# CHRMN-PROT-SHIELD.net
KiCad netlist of a schematic drawn in EAGLE
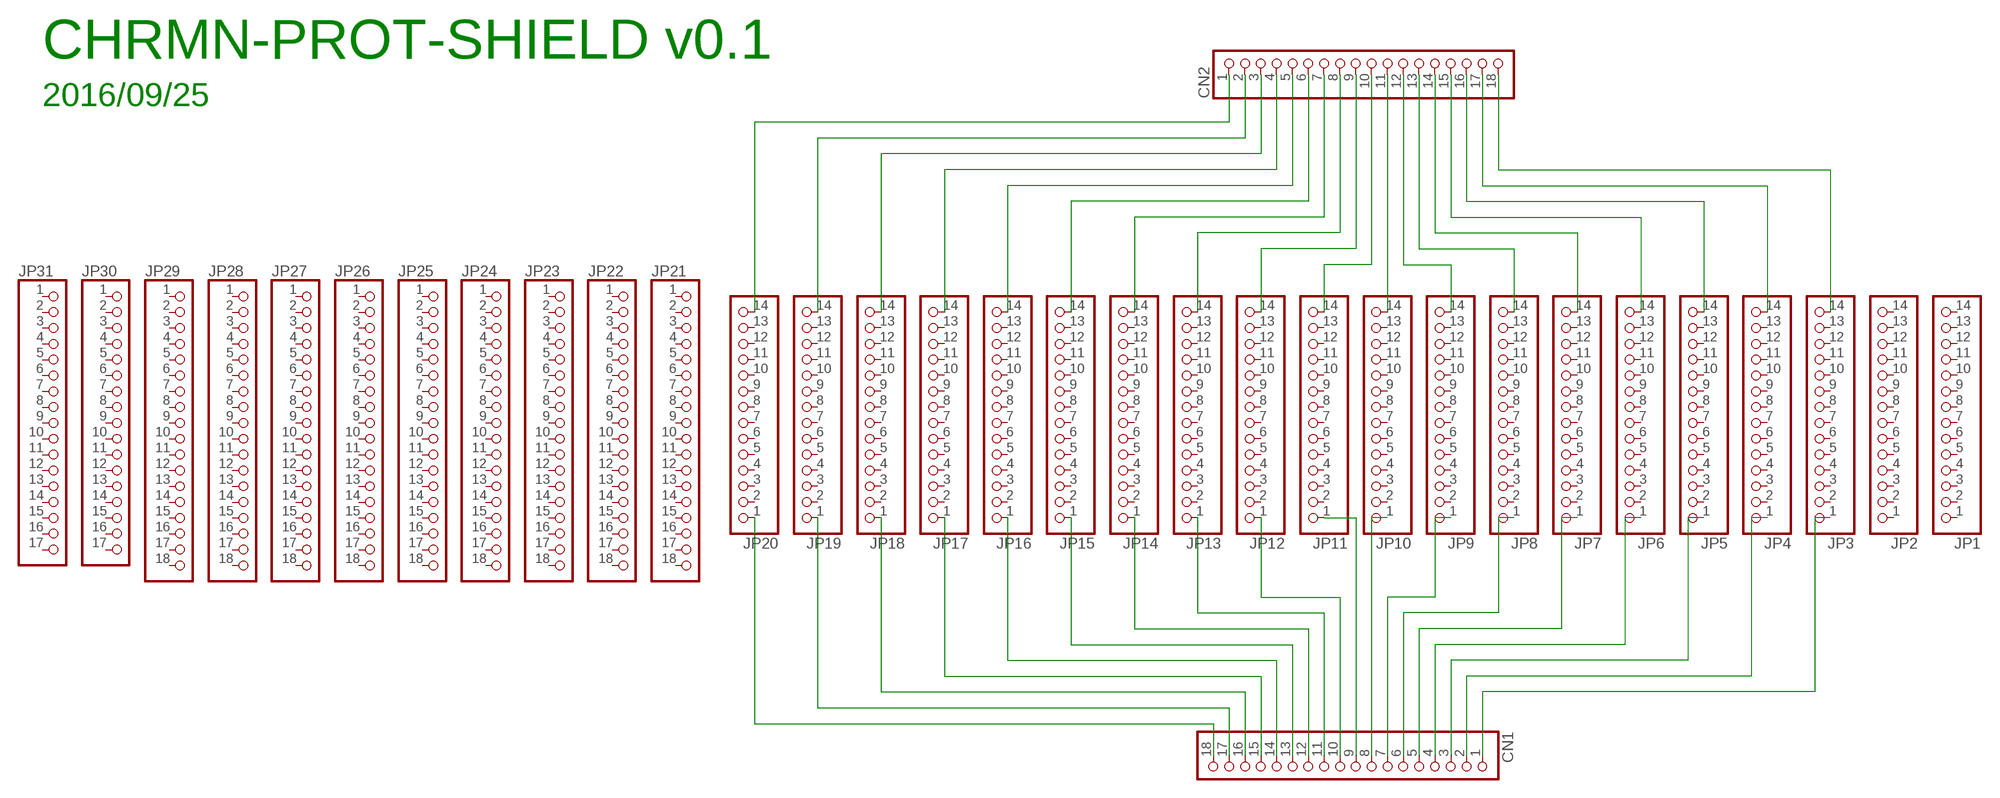
[diagram p0: schematic, sheet 1]

(export (version "E")
  (design (tool "Eeschema 10.0.6"))
  (components
    (comp (ref "CN1")
      (value "PINHD-1X18")
      (footprint "eagle-import:1X18")
      (libsource (lib "eagle-import") (part "pinhead_PINHD-1X18"))
    )
    (comp (ref "CN2")
      (value "PINHD-1X18")
      (footprint "eagle-import:1X18")
      (libsource (lib "eagle-import") (part "pinhead_PINHD-1X18"))
    )
    (comp (ref "JP1")
      (value "PINHD-1X141X14-N")
      (footprint "eagle-import:N-PHEAD-1_14")
      (libsource (lib "eagle-import") (part "PINHD-1X141X14-N"))
    )
    (comp (ref "JP2")
      (value "PINHD-1X141X14-N")
      (footprint "eagle-import:N-PHEAD-1_14")
      (libsource (lib "eagle-import") (part "PINHD-1X141X14-N"))
    )
    (comp (ref "JP3")
      (value "PINHD-1X141X14-N")
      (footprint "eagle-import:N-PHEAD-1_14")
      (libsource (lib "eagle-import") (part "PINHD-1X141X14-N"))
    )
    (comp (ref "JP4")
      (value "PINHD-1X141X14-N")
      (footprint "eagle-import:N-PHEAD-1_14")
      (libsource (lib "eagle-import") (part "PINHD-1X141X14-N"))
    )
    (comp (ref "JP5")
      (value "PINHD-1X141X14-N")
      (footprint "eagle-import:N-PHEAD-1_14")
      (libsource (lib "eagle-import") (part "PINHD-1X141X14-N"))
    )
    (comp (ref "JP6")
      (value "PINHD-1X141X14-N")
      (footprint "eagle-import:N-PHEAD-1_14")
      (libsource (lib "eagle-import") (part "PINHD-1X141X14-N"))
    )
    (comp (ref "JP7")
      (value "PINHD-1X141X14-N")
      (footprint "eagle-import:N-PHEAD-1_14")
      (libsource (lib "eagle-import") (part "PINHD-1X141X14-N"))
    )
    (comp (ref "JP8")
      (value "PINHD-1X141X14-N")
      (footprint "eagle-import:N-PHEAD-1_14")
      (libsource (lib "eagle-import") (part "PINHD-1X141X14-N"))
    )
    (comp (ref "JP9")
      (value "PINHD-1X141X14-N")
      (footprint "eagle-import:N-PHEAD-1_14")
      (libsource (lib "eagle-import") (part "PINHD-1X141X14-N"))
    )
    (comp (ref "JP10")
      (value "PINHD-1X141X14-N")
      (footprint "eagle-import:N-PHEAD-1_14")
      (libsource (lib "eagle-import") (part "PINHD-1X141X14-N"))
    )
    (comp (ref "JP11")
      (value "PINHD-1X141X14-N")
      (footprint "eagle-import:N-PHEAD-1_14")
      (libsource (lib "eagle-import") (part "PINHD-1X141X14-N"))
    )
    (comp (ref "JP12")
      (value "PINHD-1X141X14-N")
      (footprint "eagle-import:N-PHEAD-1_14")
      (libsource (lib "eagle-import") (part "PINHD-1X141X14-N"))
    )
    (comp (ref "JP13")
      (value "PINHD-1X141X14-N")
      (footprint "eagle-import:N-PHEAD-1_14")
      (libsource (lib "eagle-import") (part "PINHD-1X141X14-N"))
    )
    (comp (ref "JP14")
      (value "PINHD-1X141X14-N")
      (footprint "eagle-import:N-PHEAD-1_14")
      (libsource (lib "eagle-import") (part "PINHD-1X141X14-N"))
    )
    (comp (ref "JP15")
      (value "PINHD-1X141X14-N")
      (footprint "eagle-import:N-PHEAD-1_14")
      (libsource (lib "eagle-import") (part "PINHD-1X141X14-N"))
    )
    (comp (ref "JP16")
      (value "PINHD-1X141X14-N")
      (footprint "eagle-import:N-PHEAD-1_14")
      (libsource (lib "eagle-import") (part "PINHD-1X141X14-N"))
    )
    (comp (ref "JP17")
      (value "PINHD-1X141X14-N")
      (footprint "eagle-import:N-PHEAD-1_14")
      (libsource (lib "eagle-import") (part "PINHD-1X141X14-N"))
    )
    (comp (ref "JP18")
      (value "PINHD-1X141X14-N")
      (footprint "eagle-import:N-PHEAD-1_14")
      (libsource (lib "eagle-import") (part "PINHD-1X141X14-N"))
    )
    (comp (ref "JP19")
      (value "PINHD-1X141X14-N")
      (footprint "eagle-import:N-PHEAD-1_14")
      (libsource (lib "eagle-import") (part "PINHD-1X141X14-N"))
    )
    (comp (ref "JP20")
      (value "PINHD-1X141X14-N")
      (footprint "eagle-import:N-PHEAD-1_14")
      (libsource (lib "eagle-import") (part "PINHD-1X141X14-N"))
    )
    (comp (ref "JP21")
      (value "PINHD-1X181X18-N")
      (footprint "eagle-import:N-PHEAD-1_18")
      (libsource (lib "eagle-import") (part "PINHD-1X181X18-N"))
    )
    (comp (ref "JP22")
      (value "PINHD-1X181X18-N")
      (footprint "eagle-import:N-PHEAD-1_18")
      (libsource (lib "eagle-import") (part "PINHD-1X181X18-N"))
    )
    (comp (ref "JP23")
      (value "PINHD-1X181X18-N")
      (footprint "eagle-import:N-PHEAD-1_18")
      (libsource (lib "eagle-import") (part "PINHD-1X181X18-N"))
    )
    (comp (ref "JP24")
      (value "PINHD-1X181X18-N")
      (footprint "eagle-import:N-PHEAD-1_18")
      (libsource (lib "eagle-import") (part "PINHD-1X181X18-N"))
    )
    (comp (ref "JP25")
      (value "PINHD-1X181X18-N")
      (footprint "eagle-import:N-PHEAD-1_18")
      (libsource (lib "eagle-import") (part "PINHD-1X181X18-N"))
    )
    (comp (ref "JP26")
      (value "PINHD-1X181X18-N")
      (footprint "eagle-import:N-PHEAD-1_18")
      (libsource (lib "eagle-import") (part "PINHD-1X181X18-N"))
    )
    (comp (ref "JP27")
      (value "PINHD-1X181X18-N")
      (footprint "eagle-import:N-PHEAD-1_18")
      (libsource (lib "eagle-import") (part "PINHD-1X181X18-N"))
    )
    (comp (ref "JP28")
      (value "PINHD-1X181X18-N")
      (footprint "eagle-import:N-PHEAD-1_18")
      (libsource (lib "eagle-import") (part "PINHD-1X181X18-N"))
    )
    (comp (ref "JP29")
      (value "PINHD-1X181X18-N")
      (footprint "eagle-import:N-PHEAD-1_18")
      (libsource (lib "eagle-import") (part "PINHD-1X181X18-N"))
    )
    (comp (ref "JP30")
      (value "PINHD-1X171X17N")
      (footprint "eagle-import:N-PHEAD-1_17")
      (libsource (lib "eagle-import") (part "PINHD-1X171X17N"))
    )
    (comp (ref "JP31")
      (value "PINHD-1X171X17N")
      (footprint "eagle-import:N-PHEAD-1_17")
      (libsource (lib "eagle-import") (part "PINHD-1X171X17N"))
    )
  )
  (nets
    (net (code "1") (name "Net-(CN1-Pad1)") (class "Default")
      (node (ref "CN1") (pin "1") (pinfunction "1_1") (pintype "passive"))
      (node (ref "JP3") (pin "1") (pinfunction "1_1") (pintype "passive"))
    )
    (net (code "2") (name "Net-(CN1-Pad2)") (class "Default")
      (node (ref "CN1") (pin "2") (pinfunction "2_2") (pintype "passive"))
      (node (ref "JP4") (pin "1") (pinfunction "1_1") (pintype "passive"))
    )
    (net (code "3") (name "Net-(CN1-Pad3)") (class "Default")
      (node (ref "CN1") (pin "3") (pinfunction "3_3") (pintype "passive"))
      (node (ref "JP5") (pin "1") (pinfunction "1_1") (pintype "passive"))
    )
    (net (code "4") (name "Net-(CN1-Pad4)") (class "Default")
      (node (ref "CN1") (pin "4") (pinfunction "4_4") (pintype "passive"))
      (node (ref "JP6") (pin "1") (pinfunction "1_1") (pintype "passive"))
    )
    (net (code "5") (name "Net-(CN1-Pad5)") (class "Default")
      (node (ref "CN1") (pin "5") (pinfunction "5_5") (pintype "passive"))
      (node (ref "JP7") (pin "1") (pinfunction "1_1") (pintype "passive"))
    )
    (net (code "6") (name "Net-(CN1-Pad6)") (class "Default")
      (node (ref "CN1") (pin "6") (pinfunction "6_6") (pintype "passive"))
      (node (ref "JP8") (pin "1") (pinfunction "1_1") (pintype "passive"))
    )
    (net (code "7") (name "Net-(CN1-Pad7)") (class "Default")
      (node (ref "CN1") (pin "7") (pinfunction "7_7") (pintype "passive"))
      (node (ref "JP9") (pin "1") (pinfunction "1_1") (pintype "passive"))
    )
    (net (code "8") (name "Net-(CN1-Pad8)") (class "Default")
      (node (ref "CN1") (pin "8") (pinfunction "8_8") (pintype "passive"))
      (node (ref "JP10") (pin "1") (pinfunction "1_1") (pintype "passive"))
    )
    (net (code "9") (name "Net-(CN1-Pad9)") (class "Default")
      (node (ref "CN1") (pin "9") (pinfunction "9_9") (pintype "passive"))
      (node (ref "JP11") (pin "1") (pinfunction "1_1") (pintype "passive"))
    )
    (net (code "10") (name "Net-(CN1-Pad10)") (class "Default")
      (node (ref "CN1") (pin "10") (pinfunction "10_10") (pintype "passive"))
      (node (ref "JP12") (pin "1") (pinfunction "1_1") (pintype "passive"))
    )
    (net (code "11") (name "Net-(CN1-Pad11)") (class "Default")
      (node (ref "CN1") (pin "11") (pinfunction "11_11") (pintype "passive"))
      (node (ref "JP13") (pin "1") (pinfunction "1_1") (pintype "passive"))
    )
    (net (code "12") (name "Net-(CN1-Pad12)") (class "Default")
      (node (ref "CN1") (pin "12") (pinfunction "12_12") (pintype "passive"))
      (node (ref "JP14") (pin "1") (pinfunction "1_1") (pintype "passive"))
    )
    (net (code "13") (name "Net-(CN1-Pad13)") (class "Default")
      (node (ref "CN1") (pin "13") (pinfunction "13_13") (pintype "passive"))
      (node (ref "JP15") (pin "1") (pinfunction "1_1") (pintype "passive"))
    )
    (net (code "14") (name "Net-(CN1-Pad14)") (class "Default")
      (node (ref "CN1") (pin "14") (pinfunction "14_14") (pintype "passive"))
      (node (ref "JP16") (pin "1") (pinfunction "1_1") (pintype "passive"))
    )
    (net (code "15") (name "Net-(CN1-Pad15)") (class "Default")
      (node (ref "CN1") (pin "15") (pinfunction "15_15") (pintype "passive"))
      (node (ref "JP17") (pin "1") (pinfunction "1_1") (pintype "passive"))
    )
    (net (code "16") (name "Net-(CN1-Pad16)") (class "Default")
      (node (ref "CN1") (pin "16") (pinfunction "16_16") (pintype "passive"))
      (node (ref "JP18") (pin "1") (pinfunction "1_1") (pintype "passive"))
    )
    (net (code "17") (name "Net-(CN1-Pad17)") (class "Default")
      (node (ref "CN1") (pin "17") (pinfunction "17_17") (pintype "passive"))
      (node (ref "JP19") (pin "1") (pinfunction "1_1") (pintype "passive"))
    )
    (net (code "18") (name "Net-(CN1-Pad18)") (class "Default")
      (node (ref "CN1") (pin "18") (pinfunction "18_18") (pintype "passive"))
      (node (ref "JP20") (pin "1") (pinfunction "1_1") (pintype "passive"))
    )
    (net (code "19") (name "Net-(CN2-Pad1)") (class "Default")
      (node (ref "CN2") (pin "1") (pinfunction "1_1") (pintype "passive"))
      (node (ref "JP20") (pin "14") (pinfunction "14_14") (pintype "passive"))
    )
    (net (code "20") (name "Net-(CN2-Pad2)") (class "Default")
      (node (ref "CN2") (pin "2") (pinfunction "2_2") (pintype "passive"))
      (node (ref "JP19") (pin "14") (pinfunction "14_14") (pintype "passive"))
    )
    (net (code "21") (name "Net-(CN2-Pad3)") (class "Default")
      (node (ref "CN2") (pin "3") (pinfunction "3_3") (pintype "passive"))
      (node (ref "JP18") (pin "14") (pinfunction "14_14") (pintype "passive"))
    )
    (net (code "22") (name "Net-(CN2-Pad4)") (class "Default")
      (node (ref "CN2") (pin "4") (pinfunction "4_4") (pintype "passive"))
      (node (ref "JP17") (pin "14") (pinfunction "14_14") (pintype "passive"))
    )
    (net (code "23") (name "Net-(CN2-Pad5)") (class "Default")
      (node (ref "CN2") (pin "5") (pinfunction "5_5") (pintype "passive"))
      (node (ref "JP16") (pin "14") (pinfunction "14_14") (pintype "passive"))
    )
    (net (code "24") (name "Net-(CN2-Pad6)") (class "Default")
      (node (ref "CN2") (pin "6") (pinfunction "6_6") (pintype "passive"))
      (node (ref "JP15") (pin "14") (pinfunction "14_14") (pintype "passive"))
    )
    (net (code "25") (name "Net-(CN2-Pad7)") (class "Default")
      (node (ref "CN2") (pin "7") (pinfunction "7_7") (pintype "passive"))
      (node (ref "JP14") (pin "14") (pinfunction "14_14") (pintype "passive"))
    )
    (net (code "26") (name "Net-(CN2-Pad8)") (class "Default")
      (node (ref "CN2") (pin "8") (pinfunction "8_8") (pintype "passive"))
      (node (ref "JP13") (pin "14") (pinfunction "14_14") (pintype "passive"))
    )
    (net (code "27") (name "Net-(CN2-Pad9)") (class "Default")
      (node (ref "CN2") (pin "9") (pinfunction "9_9") (pintype "passive"))
      (node (ref "JP12") (pin "14") (pinfunction "14_14") (pintype "passive"))
    )
    (net (code "28") (name "Net-(CN2-Pad10)") (class "Default")
      (node (ref "CN2") (pin "10") (pinfunction "10_10") (pintype "passive"))
      (node (ref "JP11") (pin "14") (pinfunction "14_14") (pintype "passive"))
    )
    (net (code "29") (name "Net-(CN2-Pad11)") (class "Default")
      (node (ref "CN2") (pin "11") (pinfunction "11_11") (pintype "passive"))
      (node (ref "JP10") (pin "14") (pinfunction "14_14") (pintype "passive"))
    )
    (net (code "30") (name "Net-(CN2-Pad12)") (class "Default")
      (node (ref "CN2") (pin "12") (pinfunction "12_12") (pintype "passive"))
      (node (ref "JP9") (pin "14") (pinfunction "14_14") (pintype "passive"))
    )
    (net (code "31") (name "Net-(CN2-Pad13)") (class "Default")
      (node (ref "CN2") (pin "13") (pinfunction "13_13") (pintype "passive"))
      (node (ref "JP8") (pin "14") (pinfunction "14_14") (pintype "passive"))
    )
    (net (code "32") (name "Net-(CN2-Pad14)") (class "Default")
      (node (ref "CN2") (pin "14") (pinfunction "14_14") (pintype "passive"))
      (node (ref "JP7") (pin "14") (pinfunction "14_14") (pintype "passive"))
    )
    (net (code "33") (name "Net-(CN2-Pad15)") (class "Default")
      (node (ref "CN2") (pin "15") (pinfunction "15_15") (pintype "passive"))
      (node (ref "JP6") (pin "14") (pinfunction "14_14") (pintype "passive"))
    )
    (net (code "34") (name "Net-(CN2-Pad16)") (class "Default")
      (node (ref "CN2") (pin "16") (pinfunction "16_16") (pintype "passive"))
      (node (ref "JP5") (pin "14") (pinfunction "14_14") (pintype "passive"))
    )
    (net (code "35") (name "Net-(CN2-Pad17)") (class "Default")
      (node (ref "CN2") (pin "17") (pinfunction "17_17") (pintype "passive"))
      (node (ref "JP4") (pin "14") (pinfunction "14_14") (pintype "passive"))
    )
    (net (code "36") (name "Net-(CN2-Pad18)") (class "Default")
      (node (ref "CN2") (pin "18") (pinfunction "18_18") (pintype "passive"))
      (node (ref "JP3") (pin "14") (pinfunction "14_14") (pintype "passive"))
    )
    (net (code "37") (name "unconnected-(JP1-Pad1)") (class "Default")
      (node (ref "JP1") (pin "1") (pinfunction "1_1") (pintype "passive"))
    )
    (net (code "38") (name "unconnected-(JP1-Pad2)") (class "Default")
      (node (ref "JP1") (pin "2") (pinfunction "2_2") (pintype "passive"))
    )
    (net (code "39") (name "unconnected-(JP1-Pad3)") (class "Default")
      (node (ref "JP1") (pin "3") (pinfunction "3_3") (pintype "passive"))
    )
    (net (code "40") (name "unconnected-(JP1-Pad4)") (class "Default")
      (node (ref "JP1") (pin "4") (pinfunction "4_4") (pintype "passive"))
    )
    (net (code "41") (name "unconnected-(JP1-Pad5)") (class "Default")
      (node (ref "JP1") (pin "5") (pinfunction "5_5") (pintype "passive"))
    )
    (net (code "42") (name "unconnected-(JP1-Pad6)") (class "Default")
      (node (ref "JP1") (pin "6") (pinfunction "6_6") (pintype "passive"))
    )
    (net (code "43") (name "unconnected-(JP1-Pad7)") (class "Default")
      (node (ref "JP1") (pin "7") (pinfunction "7_7") (pintype "passive"))
    )
    (net (code "44") (name "unconnected-(JP1-Pad8)") (class "Default")
      (node (ref "JP1") (pin "8") (pinfunction "8_8") (pintype "passive"))
    )
    (net (code "45") (name "unconnected-(JP1-Pad9)") (class "Default")
      (node (ref "JP1") (pin "9") (pinfunction "9_9") (pintype "passive"))
    )
    (net (code "46") (name "unconnected-(JP1-Pad10)") (class "Default")
      (node (ref "JP1") (pin "10") (pinfunction "10_10") (pintype "passive"))
    )
    (net (code "47") (name "unconnected-(JP1-Pad11)") (class "Default")
      (node (ref "JP1") (pin "11") (pinfunction "11_11") (pintype "passive"))
    )
    (net (code "48") (name "unconnected-(JP1-Pad12)") (class "Default")
      (node (ref "JP1") (pin "12") (pinfunction "12_12") (pintype "passive"))
    )
    (net (code "49") (name "unconnected-(JP1-Pad13)") (class "Default")
      (node (ref "JP1") (pin "13") (pinfunction "13_13") (pintype "passive"))
    )
    (net (code "50") (name "unconnected-(JP1-Pad14)") (class "Default")
      (node (ref "JP1") (pin "14") (pinfunction "14_14") (pintype "passive"))
    )
    (net (code "51") (name "unconnected-(JP2-Pad1)") (class "Default")
      (node (ref "JP2") (pin "1") (pinfunction "1_1") (pintype "passive"))
    )
    (net (code "52") (name "unconnected-(JP2-Pad2)") (class "Default")
      (node (ref "JP2") (pin "2") (pinfunction "2_2") (pintype "passive"))
    )
    (net (code "53") (name "unconnected-(JP2-Pad3)") (class "Default")
      (node (ref "JP2") (pin "3") (pinfunction "3_3") (pintype "passive"))
    )
    (net (code "54") (name "unconnected-(JP2-Pad4)") (class "Default")
      (node (ref "JP2") (pin "4") (pinfunction "4_4") (pintype "passive"))
    )
    (net (code "55") (name "unconnected-(JP2-Pad5)") (class "Default")
      (node (ref "JP2") (pin "5") (pinfunction "5_5") (pintype "passive"))
    )
    (net (code "56") (name "unconnected-(JP2-Pad6)") (class "Default")
      (node (ref "JP2") (pin "6") (pinfunction "6_6") (pintype "passive"))
    )
    (net (code "57") (name "unconnected-(JP2-Pad7)") (class "Default")
      (node (ref "JP2") (pin "7") (pinfunction "7_7") (pintype "passive"))
    )
    (net (code "58") (name "unconnected-(JP2-Pad8)") (class "Default")
      (node (ref "JP2") (pin "8") (pinfunction "8_8") (pintype "passive"))
    )
    (net (code "59") (name "unconnected-(JP2-Pad9)") (class "Default")
      (node (ref "JP2") (pin "9") (pinfunction "9_9") (pintype "passive"))
    )
    (net (code "60") (name "unconnected-(JP2-Pad10)") (class "Default")
      (node (ref "JP2") (pin "10") (pinfunction "10_10") (pintype "passive"))
    )
    (net (code "61") (name "unconnected-(JP2-Pad11)") (class "Default")
      (node (ref "JP2") (pin "11") (pinfunction "11_11") (pintype "passive"))
    )
    (net (code "62") (name "unconnected-(JP2-Pad12)") (class "Default")
      (node (ref "JP2") (pin "12") (pinfunction "12_12") (pintype "passive"))
    )
    (net (code "63") (name "unconnected-(JP2-Pad13)") (class "Default")
      (node (ref "JP2") (pin "13") (pinfunction "13_13") (pintype "passive"))
    )
    (net (code "64") (name "unconnected-(JP2-Pad14)") (class "Default")
      (node (ref "JP2") (pin "14") (pinfunction "14_14") (pintype "passive"))
    )
    (net (code "65") (name "unconnected-(JP3-Pad2)") (class "Default")
      (node (ref "JP3") (pin "2") (pinfunction "2_2") (pintype "passive"))
    )
    (net (code "66") (name "unconnected-(JP3-Pad3)") (class "Default")
      (node (ref "JP3") (pin "3") (pinfunction "3_3") (pintype "passive"))
    )
    (net (code "67") (name "unconnected-(JP3-Pad4)") (class "Default")
      (node (ref "JP3") (pin "4") (pinfunction "4_4") (pintype "passive"))
    )
    (net (code "68") (name "unconnected-(JP3-Pad5)") (class "Default")
      (node (ref "JP3") (pin "5") (pinfunction "5_5") (pintype "passive"))
    )
    (net (code "69") (name "unconnected-(JP3-Pad6)") (class "Default")
      (node (ref "JP3") (pin "6") (pinfunction "6_6") (pintype "passive"))
    )
    (net (code "70") (name "unconnected-(JP3-Pad7)") (class "Default")
      (node (ref "JP3") (pin "7") (pinfunction "7_7") (pintype "passive"))
    )
    (net (code "71") (name "unconnected-(JP3-Pad8)") (class "Default")
      (node (ref "JP3") (pin "8") (pinfunction "8_8") (pintype "passive"))
    )
    (net (code "72") (name "unconnected-(JP3-Pad9)") (class "Default")
      (node (ref "JP3") (pin "9") (pinfunction "9_9") (pintype "passive"))
    )
    (net (code "73") (name "unconnected-(JP3-Pad10)") (class "Default")
      (node (ref "JP3") (pin "10") (pinfunction "10_10") (pintype "passive"))
    )
    (net (code "74") (name "unconnected-(JP3-Pad11)") (class "Default")
      (node (ref "JP3") (pin "11") (pinfunction "11_11") (pintype "passive"))
    )
    (net (code "75") (name "unconnected-(JP3-Pad12)") (class "Default")
      (node (ref "JP3") (pin "12") (pinfunction "12_12") (pintype "passive"))
    )
    (net (code "76") (name "unconnected-(JP3-Pad13)") (class "Default")
      (node (ref "JP3") (pin "13") (pinfunction "13_13") (pintype "passive"))
    )
    (net (code "77") (name "unconnected-(JP4-Pad2)") (class "Default")
      (node (ref "JP4") (pin "2") (pinfunction "2_2") (pintype "passive"))
    )
    (net (code "78") (name "unconnected-(JP4-Pad3)") (class "Default")
      (node (ref "JP4") (pin "3") (pinfunction "3_3") (pintype "passive"))
    )
    (net (code "79") (name "unconnected-(JP4-Pad4)") (class "Default")
      (node (ref "JP4") (pin "4") (pinfunction "4_4") (pintype "passive"))
    )
    (net (code "80") (name "unconnected-(JP4-Pad5)") (class "Default")
      (node (ref "JP4") (pin "5") (pinfunction "5_5") (pintype "passive"))
    )
    (net (code "81") (name "unconnected-(JP4-Pad6)") (class "Default")
      (node (ref "JP4") (pin "6") (pinfunction "6_6") (pintype "passive"))
    )
    (net (code "82") (name "unconnected-(JP4-Pad7)") (class "Default")
      (node (ref "JP4") (pin "7") (pinfunction "7_7") (pintype "passive"))
    )
    (net (code "83") (name "unconnected-(JP4-Pad8)") (class "Default")
      (node (ref "JP4") (pin "8") (pinfunction "8_8") (pintype "passive"))
    )
    (net (code "84") (name "unconnected-(JP4-Pad9)") (class "Default")
      (node (ref "JP4") (pin "9") (pinfunction "9_9") (pintype "passive"))
    )
    (net (code "85") (name "unconnected-(JP4-Pad10)") (class "Default")
      (node (ref "JP4") (pin "10") (pinfunction "10_10") (pintype "passive"))
    )
    (net (code "86") (name "unconnected-(JP4-Pad11)") (class "Default")
      (node (ref "JP4") (pin "11") (pinfunction "11_11") (pintype "passive"))
    )
    (net (code "87") (name "unconnected-(JP4-Pad12)") (class "Default")
      (node (ref "JP4") (pin "12") (pinfunction "12_12") (pintype "passive"))
    )
    (net (code "88") (name "unconnected-(JP4-Pad13)") (class "Default")
      (node (ref "JP4") (pin "13") (pinfunction "13_13") (pintype "passive"))
    )
    (net (code "89") (name "unconnected-(JP5-Pad2)") (class "Default")
      (node (ref "JP5") (pin "2") (pinfunction "2_2") (pintype "passive"))
    )
    (net (code "90") (name "unconnected-(JP5-Pad3)") (class "Default")
      (node (ref "JP5") (pin "3") (pinfunction "3_3") (pintype "passive"))
    )
    (net (code "91") (name "unconnected-(JP5-Pad4)") (class "Default")
      (node (ref "JP5") (pin "4") (pinfunction "4_4") (pintype "passive"))
    )
    (net (code "92") (name "unconnected-(JP5-Pad5)") (class "Default")
      (node (ref "JP5") (pin "5") (pinfunction "5_5") (pintype "passive"))
    )
    (net (code "93") (name "unconnected-(JP5-Pad6)") (class "Default")
      (node (ref "JP5") (pin "6") (pinfunction "6_6") (pintype "passive"))
    )
    (net (code "94") (name "unconnected-(JP5-Pad7)") (class "Default")
      (node (ref "JP5") (pin "7") (pinfunction "7_7") (pintype "passive"))
    )
    (net (code "95") (name "unconnected-(JP5-Pad8)") (class "Default")
      (node (ref "JP5") (pin "8") (pinfunction "8_8") (pintype "passive"))
    )
    (net (code "96") (name "unconnected-(JP5-Pad9)") (class "Default")
      (node (ref "JP5") (pin "9") (pinfunction "9_9") (pintype "passive"))
    )
    (net (code "97") (name "unconnected-(JP5-Pad10)") (class "Default")
      (node (ref "JP5") (pin "10") (pinfunction "10_10") (pintype "passive"))
    )
    (net (code "98") (name "unconnected-(JP5-Pad11)") (class "Default")
      (node (ref "JP5") (pin "11") (pinfunction "11_11") (pintype "passive"))
    )
    (net (code "99") (name "unconnected-(JP5-Pad12)") (class "Default")
      (node (ref "JP5") (pin "12") (pinfunction "12_12") (pintype "passive"))
    )
    (net (code "100") (name "unconnected-(JP5-Pad13)") (class "Default")
      (node (ref "JP5") (pin "13") (pinfunction "13_13") (pintype "passive"))
    )
    (net (code "101") (name "unconnected-(JP6-Pad2)") (class "Default")
      (node (ref "JP6") (pin "2") (pinfunction "2_2") (pintype "passive"))
    )
    (net (code "102") (name "unconnected-(JP6-Pad3)") (class "Default")
      (node (ref "JP6") (pin "3") (pinfunction "3_3") (pintype "passive"))
    )
    (net (code "103") (name "unconnected-(JP6-Pad4)") (class "Default")
      (node (ref "JP6") (pin "4") (pinfunction "4_4") (pintype "passive"))
    )
    (net (code "104") (name "unconnected-(JP6-Pad5)") (class "Default")
      (node (ref "JP6") (pin "5") (pinfunction "5_5") (pintype "passive"))
    )
    (net (code "105") (name "unconnected-(JP6-Pad6)") (class "Default")
      (node (ref "JP6") (pin "6") (pinfunction "6_6") (pintype "passive"))
    )
    (net (code "106") (name "unconnected-(JP6-Pad7)") (class "Default")
      (node (ref "JP6") (pin "7") (pinfunction "7_7") (pintype "passive"))
    )
    (net (code "107") (name "unconnected-(JP6-Pad8)") (class "Default")
      (node (ref "JP6") (pin "8") (pinfunction "8_8") (pintype "passive"))
    )
    (net (code "108") (name "unconnected-(JP6-Pad9)") (class "Default")
      (node (ref "JP6") (pin "9") (pinfunction "9_9") (pintype "passive"))
    )
    (net (code "109") (name "unconnected-(JP6-Pad10)") (class "Default")
      (node (ref "JP6") (pin "10") (pinfunction "10_10") (pintype "passive"))
    )
    (net (code "110") (name "unconnected-(JP6-Pad11)") (class "Default")
      (node (ref "JP6") (pin "11") (pinfunction "11_11") (pintype "passive"))
    )
    (net (code "111") (name "unconnected-(JP6-Pad12)") (class "Default")
      (node (ref "JP6") (pin "12") (pinfunction "12_12") (pintype "passive"))
    )
    (net (code "112") (name "unconnected-(JP6-Pad13)") (class "Default")
      (node (ref "JP6") (pin "13") (pinfunction "13_13") (pintype "passive"))
    )
    (net (code "113") (name "unconnected-(JP7-Pad2)") (class "Default")
      (node (ref "JP7") (pin "2") (pinfunction "2_2") (pintype "passive"))
    )
    (net (code "114") (name "unconnected-(JP7-Pad3)") (class "Default")
      (node (ref "JP7") (pin "3") (pinfunction "3_3") (pintype "passive"))
    )
    (net (code "115") (name "unconnected-(JP7-Pad4)") (class "Default")
      (node (ref "JP7") (pin "4") (pinfunction "4_4") (pintype "passive"))
    )
    (net (code "116") (name "unconnected-(JP7-Pad5)") (class "Default")
      (node (ref "JP7") (pin "5") (pinfunction "5_5") (pintype "passive"))
    )
    (net (code "117") (name "unconnected-(JP7-Pad6)") (class "Default")
      (node (ref "JP7") (pin "6") (pinfunction "6_6") (pintype "passive"))
    )
    (net (code "118") (name "unconnected-(JP7-Pad7)") (class "Default")
      (node (ref "JP7") (pin "7") (pinfunction "7_7") (pintype "passive"))
    )
    (net (code "119") (name "unconnected-(JP7-Pad8)") (class "Default")
      (node (ref "JP7") (pin "8") (pinfunction "8_8") (pintype "passive"))
    )
    (net (code "120") (name "unconnected-(JP7-Pad9)") (class "Default")
      (node (ref "JP7") (pin "9") (pinfunction "9_9") (pintype "passive"))
    )
    (net (code "121") (name "unconnected-(JP7-Pad10)") (class "Default")
      (node (ref "JP7") (pin "10") (pinfunction "10_10") (pintype "passive"))
    )
    (net (code "122") (name "unconnected-(JP7-Pad11)") (class "Default")
      (node (ref "JP7") (pin "11") (pinfunction "11_11") (pintype "passive"))
    )
    (net (code "123") (name "unconnected-(JP7-Pad12)") (class "Default")
      (node (ref "JP7") (pin "12") (pinfunction "12_12") (pintype "passive"))
    )
    (net (code "124") (name "unconnected-(JP7-Pad13)") (class "Default")
      (node (ref "JP7") (pin "13") (pinfunction "13_13") (pintype "passive"))
    )
    (net (code "125") (name "unconnected-(JP8-Pad2)") (class "Default")
      (node (ref "JP8") (pin "2") (pinfunction "2_2") (pintype "passive"))
    )
    (net (code "126") (name "unconnected-(JP8-Pad3)") (class "Default")
      (node (ref "JP8") (pin "3") (pinfunction "3_3") (pintype "passive"))
    )
    (net (code "127") (name "unconnected-(JP8-Pad4)") (class "Default")
      (node (ref "JP8") (pin "4") (pinfunction "4_4") (pintype "passive"))
    )
    (net (code "128") (name "unconnected-(JP8-Pad5)") (class "Default")
      (node (ref "JP8") (pin "5") (pinfunction "5_5") (pintype "passive"))
    )
    (net (code "129") (name "unconnected-(JP8-Pad6)") (class "Default")
      (node (ref "JP8") (pin "6") (pinfunction "6_6") (pintype "passive"))
    )
    (net (code "130") (name "unconnected-(JP8-Pad7)") (class "Default")
      (node (ref "JP8") (pin "7") (pinfunction "7_7") (pintype "passive"))
    )
    (net (code "131") (name "unconnected-(JP8-Pad8)") (class "Default")
      (node (ref "JP8") (pin "8") (pinfunction "8_8") (pintype "passive"))
    )
    (net (code "132") (name "unconnected-(JP8-Pad9)") (class "Default")
      (node (ref "JP8") (pin "9") (pinfunction "9_9") (pintype "passive"))
    )
    (net (code "133") (name "unconnected-(JP8-Pad10)") (class "Default")
      (node (ref "JP8") (pin "10") (pinfunction "10_10") (pintype "passive"))
    )
    (net (code "134") (name "unconnected-(JP8-Pad11)") (class "Default")
      (node (ref "JP8") (pin "11") (pinfunction "11_11") (pintype "passive"))
    )
    (net (code "135") (name "unconnected-(JP8-Pad12)") (class "Default")
      (node (ref "JP8") (pin "12") (pinfunction "12_12") (pintype "passive"))
    )
    (net (code "136") (name "unconnected-(JP8-Pad13)") (class "Default")
      (node (ref "JP8") (pin "13") (pinfunction "13_13") (pintype "passive"))
    )
    (net (code "137") (name "unconnected-(JP9-Pad2)") (class "Default")
      (node (ref "JP9") (pin "2") (pinfunction "2_2") (pintype "passive"))
    )
    (net (code "138") (name "unconnected-(JP9-Pad3)") (class "Default")
      (node (ref "JP9") (pin "3") (pinfunction "3_3") (pintype "passive"))
    )
    (net (code "139") (name "unconnected-(JP9-Pad4)") (class "Default")
      (node (ref "JP9") (pin "4") (pinfunction "4_4") (pintype "passive"))
    )
    (net (code "140") (name "unconnected-(JP9-Pad5)") (class "Default")
      (node (ref "JP9") (pin "5") (pinfunction "5_5") (pintype "passive"))
    )
    (net (code "141") (name "unconnected-(JP9-Pad6)") (class "Default")
      (node (ref "JP9") (pin "6") (pinfunction "6_6") (pintype "passive"))
    )
    (net (code "142") (name "unconnected-(JP9-Pad7)") (class "Default")
      (node (ref "JP9") (pin "7") (pinfunction "7_7") (pintype "passive"))
    )
    (net (code "143") (name "unconnected-(JP9-Pad8)") (class "Default")
      (node (ref "JP9") (pin "8") (pinfunction "8_8") (pintype "passive"))
    )
    (net (code "144") (name "unconnected-(JP9-Pad9)") (class "Default")
      (node (ref "JP9") (pin "9") (pinfunction "9_9") (pintype "passive"))
    )
    (net (code "145") (name "unconnected-(JP9-Pad10)") (class "Default")
      (node (ref "JP9") (pin "10") (pinfunction "10_10") (pintype "passive"))
    )
    (net (code "146") (name "unconnected-(JP9-Pad11)") (class "Default")
      (node (ref "JP9") (pin "11") (pinfunction "11_11") (pintype "passive"))
    )
    (net (code "147") (name "unconnected-(JP9-Pad12)") (class "Default")
      (node (ref "JP9") (pin "12") (pinfunction "12_12") (pintype "passive"))
    )
    (net (code "148") (name "unconnected-(JP9-Pad13)") (class "Default")
      (node (ref "JP9") (pin "13") (pinfunction "13_13") (pintype "passive"))
    )
    (net (code "149") (name "unconnected-(JP10-Pad2)") (class "Default")
      (node (ref "JP10") (pin "2") (pinfunction "2_2") (pintype "passive"))
    )
    (net (code "150") (name "unconnected-(JP10-Pad3)") (class "Default")
      (node (ref "JP10") (pin "3") (pinfunction "3_3") (pintype "passive"))
    )
    (net (code "151") (name "unconnected-(JP10-Pad4)") (class "Default")
      (node (ref "JP10") (pin "4") (pinfunction "4_4") (pintype "passive"))
    )
    (net (code "152") (name "unconnected-(JP10-Pad5)") (class "Default")
      (node (ref "JP10") (pin "5") (pinfunction "5_5") (pintype "passive"))
    )
    (net (code "153") (name "unconnected-(JP10-Pad6)") (class "Default")
      (node (ref "JP10") (pin "6") (pinfunction "6_6") (pintype "passive"))
    )
    (net (code "154") (name "unconnected-(JP10-Pad7)") (class "Default")
      (node (ref "JP10") (pin "7") (pinfunction "7_7") (pintype "passive"))
    )
    (net (code "155") (name "unconnected-(JP10-Pad8)") (class "Default")
      (node (ref "JP10") (pin "8") (pinfunction "8_8") (pintype "passive"))
    )
    (net (code "156") (name "unconnected-(JP10-Pad9)") (class "Default")
      (node (ref "JP10") (pin "9") (pinfunction "9_9") (pintype "passive"))
    )
    (net (code "157") (name "unconnected-(JP10-Pad10)") (class "Default")
      (node (ref "JP10") (pin "10") (pinfunction "10_10") (pintype "passive"))
    )
    (net (code "158") (name "unconnected-(JP10-Pad11)") (class "Default")
      (node (ref "JP10") (pin "11") (pinfunction "11_11") (pintype "passive"))
    )
    (net (code "159") (name "unconnected-(JP10-Pad12)") (class "Default")
      (node (ref "JP10") (pin "12") (pinfunction "12_12") (pintype "passive"))
    )
    (net (code "160") (name "unconnected-(JP10-Pad13)") (class "Default")
      (node (ref "JP10") (pin "13") (pinfunction "13_13") (pintype "passive"))
    )
    (net (code "161") (name "unconnected-(JP11-Pad2)") (class "Default")
      (node (ref "JP11") (pin "2") (pinfunction "2_2") (pintype "passive"))
    )
    (net (code "162") (name "unconnected-(JP11-Pad3)") (class "Default")
      (node (ref "JP11") (pin "3") (pinfunction "3_3") (pintype "passive"))
    )
    (net (code "163") (name "unconnected-(JP11-Pad4)") (class "Default")
      (node (ref "JP11") (pin "4") (pinfunction "4_4") (pintype "passive"))
    )
    (net (code "164") (name "unconnected-(JP11-Pad5)") (class "Default")
      (node (ref "JP11") (pin "5") (pinfunction "5_5") (pintype "passive"))
    )
    (net (code "165") (name "unconnected-(JP11-Pad6)") (class "Default")
      (node (ref "JP11") (pin "6") (pinfunction "6_6") (pintype "passive"))
    )
    (net (code "166") (name "unconnected-(JP11-Pad7)") (class "Default")
      (node (ref "JP11") (pin "7") (pinfunction "7_7") (pintype "passive"))
    )
    (net (code "167") (name "unconnected-(JP11-Pad8)") (class "Default")
      (node (ref "JP11") (pin "8") (pinfunction "8_8") (pintype "passive"))
    )
    (net (code "168") (name "unconnected-(JP11-Pad9)") (class "Default")
      (node (ref "JP11") (pin "9") (pinfunction "9_9") (pintype "passive"))
    )
    (net (code "169") (name "unconnected-(JP11-Pad10)") (class "Default")
      (node (ref "JP11") (pin "10") (pinfunction "10_10") (pintype "passive"))
    )
    (net (code "170") (name "unconnected-(JP11-Pad11)") (class "Default")
      (node (ref "JP11") (pin "11") (pinfunction "11_11") (pintype "passive"))
    )
    (net (code "171") (name "unconnected-(JP11-Pad12)") (class "Default")
      (node (ref "JP11") (pin "12") (pinfunction "12_12") (pintype "passive"))
    )
    (net (code "172") (name "unconnected-(JP11-Pad13)") (class "Default")
      (node (ref "JP11") (pin "13") (pinfunction "13_13") (pintype "passive"))
    )
    (net (code "173") (name "unconnected-(JP12-Pad2)") (class "Default")
      (node (ref "JP12") (pin "2") (pinfunction "2_2") (pintype "passive"))
    )
    (net (code "174") (name "unconnected-(JP12-Pad3)") (class "Default")
      (node (ref "JP12") (pin "3") (pinfunction "3_3") (pintype "passive"))
    )
    (net (code "175") (name "unconnected-(JP12-Pad4)") (class "Default")
      (node (ref "JP12") (pin "4") (pinfunction "4_4") (pintype "passive"))
    )
    (net (code "176") (name "unconnected-(JP12-Pad5)") (class "Default")
      (node (ref "JP12") (pin "5") (pinfunction "5_5") (pintype "passive"))
    )
    (net (code "177") (name "unconnected-(JP12-Pad6)") (class "Default")
      (node (ref "JP12") (pin "6") (pinfunction "6_6") (pintype "passive"))
    )
    (net (code "178") (name "unconnected-(JP12-Pad7)") (class "Default")
      (node (ref "JP12") (pin "7") (pinfunction "7_7") (pintype "passive"))
    )
    (net (code "179") (name "unconnected-(JP12-Pad8)") (class "Default")
      (node (ref "JP12") (pin "8") (pinfunction "8_8") (pintype "passive"))
    )
    (net (code "180") (name "unconnected-(JP12-Pad9)") (class "Default")
      (node (ref "JP12") (pin "9") (pinfunction "9_9") (pintype "passive"))
    )
    (net (code "181") (name "unconnected-(JP12-Pad10)") (class "Default")
      (node (ref "JP12") (pin "10") (pinfunction "10_10") (pintype "passive"))
    )
    (net (code "182") (name "unconnected-(JP12-Pad11)") (class "Default")
      (node (ref "JP12") (pin "11") (pinfunction "11_11") (pintype "passive"))
    )
    (net (code "183") (name "unconnected-(JP12-Pad12)") (class "Default")
      (node (ref "JP12") (pin "12") (pinfunction "12_12") (pintype "passive"))
    )
    (net (code "184") (name "unconnected-(JP12-Pad13)") (class "Default")
      (node (ref "JP12") (pin "13") (pinfunction "13_13") (pintype "passive"))
    )
    (net (code "185") (name "unconnected-(JP13-Pad2)") (class "Default")
      (node (ref "JP13") (pin "2") (pinfunction "2_2") (pintype "passive"))
    )
    (net (code "186") (name "unconnected-(JP13-Pad3)") (class "Default")
      (node (ref "JP13") (pin "3") (pinfunction "3_3") (pintype "passive"))
    )
    (net (code "187") (name "unconnected-(JP13-Pad4)") (class "Default")
      (node (ref "JP13") (pin "4") (pinfunction "4_4") (pintype "passive"))
    )
    (net (code "188") (name "unconnected-(JP13-Pad5)") (class "Default")
      (node (ref "JP13") (pin "5") (pinfunction "5_5") (pintype "passive"))
    )
    (net (code "189") (name "unconnected-(JP13-Pad6)") (class "Default")
      (node (ref "JP13") (pin "6") (pinfunction "6_6") (pintype "passive"))
    )
    (net (code "190") (name "unconnected-(JP13-Pad7)") (class "Default")
      (node (ref "JP13") (pin "7") (pinfunction "7_7") (pintype "passive"))
    )
    (net (code "191") (name "unconnected-(JP13-Pad8)") (class "Default")
      (node (ref "JP13") (pin "8") (pinfunction "8_8") (pintype "passive"))
    )
    (net (code "192") (name "unconnected-(JP13-Pad9)") (class "Default")
      (node (ref "JP13") (pin "9") (pinfunction "9_9") (pintype "passive"))
    )
    (net (code "193") (name "unconnected-(JP13-Pad10)") (class "Default")
      (node (ref "JP13") (pin "10") (pinfunction "10_10") (pintype "passive"))
    )
    (net (code "194") (name "unconnected-(JP13-Pad11)") (class "Default")
      (node (ref "JP13") (pin "11") (pinfunction "11_11") (pintype "passive"))
    )
    (net (code "195") (name "unconnected-(JP13-Pad12)") (class "Default")
      (node (ref "JP13") (pin "12") (pinfunction "12_12") (pintype "passive"))
    )
    (net (code "196") (name "unconnected-(JP13-Pad13)") (class "Default")
      (node (ref "JP13") (pin "13") (pinfunction "13_13") (pintype "passive"))
    )
    (net (code "197") (name "unconnected-(JP14-Pad2)") (class "Default")
      (node (ref "JP14") (pin "2") (pinfunction "2_2") (pintype "passive"))
    )
    (net (code "198") (name "unconnected-(JP14-Pad3)") (class "Default")
      (node (ref "JP14") (pin "3") (pinfunction "3_3") (pintype "passive"))
    )
    (net (code "199") (name "unconnected-(JP14-Pad4)") (class "Default")
      (node (ref "JP14") (pin "4") (pinfunction "4_4") (pintype "passive"))
    )
    (net (code "200") (name "unconnected-(JP14-Pad5)") (class "Default")
      (node (ref "JP14") (pin "5") (pinfunction "5_5") (pintype "passive"))
    )
    (net (code "201") (name "unconnected-(JP14-Pad6)") (class "Default")
      (node (ref "JP14") (pin "6") (pinfunction "6_6") (pintype "passive"))
    )
    (net (code "202") (name "unconnected-(JP14-Pad7)") (class "Default")
      (node (ref "JP14") (pin "7") (pinfunction "7_7") (pintype "passive"))
    )
    (net (code "203") (name "unconnected-(JP14-Pad8)") (class "Default")
      (node (ref "JP14") (pin "8") (pinfunction "8_8") (pintype "passive"))
    )
    (net (code "204") (name "unconnected-(JP14-Pad9)") (class "Default")
      (node (ref "JP14") (pin "9") (pinfunction "9_9") (pintype "passive"))
    )
    (net (code "205") (name "unconnected-(JP14-Pad10)") (class "Default")
      (node (ref "JP14") (pin "10") (pinfunction "10_10") (pintype "passive"))
    )
    (net (code "206") (name "unconnected-(JP14-Pad11)") (class "Default")
      (node (ref "JP14") (pin "11") (pinfunction "11_11") (pintype "passive"))
    )
    (net (code "207") (name "unconnected-(JP14-Pad12)") (class "Default")
      (node (ref "JP14") (pin "12") (pinfunction "12_12") (pintype "passive"))
    )
    (net (code "208") (name "unconnected-(JP14-Pad13)") (class "Default")
      (node (ref "JP14") (pin "13") (pinfunction "13_13") (pintype "passive"))
    )
    (net (code "209") (name "unconnected-(JP15-Pad2)") (class "Default")
      (node (ref "JP15") (pin "2") (pinfunction "2_2") (pintype "passive"))
    )
    (net (code "210") (name "unconnected-(JP15-Pad3)") (class "Default")
      (node (ref "JP15") (pin "3") (pinfunction "3_3") (pintype "passive"))
    )
    (net (code "211") (name "unconnected-(JP15-Pad4)") (class "Default")
      (node (ref "JP15") (pin "4") (pinfunction "4_4") (pintype "passive"))
    )
    (net (code "212") (name "unconnected-(JP15-Pad5)") (class "Default")
      (node (ref "JP15") (pin "5") (pinfunction "5_5") (pintype "passive"))
    )
    (net (code "213") (name "unconnected-(JP15-Pad6)") (class "Default")
      (node (ref "JP15") (pin "6") (pinfunction "6_6") (pintype "passive"))
    )
    (net (code "214") (name "unconnected-(JP15-Pad7)") (class "Default")
      (node (ref "JP15") (pin "7") (pinfunction "7_7") (pintype "passive"))
    )
    (net (code "215") (name "unconnected-(JP15-Pad8)") (class "Default")
      (node (ref "JP15") (pin "8") (pinfunction "8_8") (pintype "passive"))
    )
    (net (code "216") (name "unconnected-(JP15-Pad9)") (class "Default")
      (node (ref "JP15") (pin "9") (pinfunction "9_9") (pintype "passive"))
    )
    (net (code "217") (name "unconnected-(JP15-Pad10)") (class "Default")
      (node (ref "JP15") (pin "10") (pinfunction "10_10") (pintype "passive"))
    )
    (net (code "218") (name "unconnected-(JP15-Pad11)") (class "Default")
      (node (ref "JP15") (pin "11") (pinfunction "11_11") (pintype "passive"))
    )
    (net (code "219") (name "unconnected-(JP15-Pad12)") (class "Default")
      (node (ref "JP15") (pin "12") (pinfunction "12_12") (pintype "passive"))
    )
    (net (code "220") (name "unconnected-(JP15-Pad13)") (class "Default")
      (node (ref "JP15") (pin "13") (pinfunction "13_13") (pintype "passive"))
    )
    (net (code "221") (name "unconnected-(JP16-Pad2)") (class "Default")
      (node (ref "JP16") (pin "2") (pinfunction "2_2") (pintype "passive"))
    )
    (net (code "222") (name "unconnected-(JP16-Pad3)") (class "Default")
      (node (ref "JP16") (pin "3") (pinfunction "3_3") (pintype "passive"))
    )
    (net (code "223") (name "unconnected-(JP16-Pad4)") (class "Default")
      (node (ref "JP16") (pin "4") (pinfunction "4_4") (pintype "passive"))
    )
    (net (code "224") (name "unconnected-(JP16-Pad5)") (class "Default")
      (node (ref "JP16") (pin "5") (pinfunction "5_5") (pintype "passive"))
    )
    (net (code "225") (name "unconnected-(JP16-Pad6)") (class "Default")
      (node (ref "JP16") (pin "6") (pinfunction "6_6") (pintype "passive"))
    )
    (net (code "226") (name "unconnected-(JP16-Pad7)") (class "Default")
      (node (ref "JP16") (pin "7") (pinfunction "7_7") (pintype "passive"))
    )
    (net (code "227") (name "unconnected-(JP16-Pad8)") (class "Default")
      (node (ref "JP16") (pin "8") (pinfunction "8_8") (pintype "passive"))
    )
    (net (code "228") (name "unconnected-(JP16-Pad9)") (class "Default")
      (node (ref "JP16") (pin "9") (pinfunction "9_9") (pintype "passive"))
    )
    (net (code "229") (name "unconnected-(JP16-Pad10)") (class "Default")
      (node (ref "JP16") (pin "10") (pinfunction "10_10") (pintype "passive"))
    )
    (net (code "230") (name "unconnected-(JP16-Pad11)") (class "Default")
      (node (ref "JP16") (pin "11") (pinfunction "11_11") (pintype "passive"))
    )
    (net (code "231") (name "unconnected-(JP16-Pad12)") (class "Default")
      (node (ref "JP16") (pin "12") (pinfunction "12_12") (pintype "passive"))
    )
    (net (code "232") (name "unconnected-(JP16-Pad13)") (class "Default")
      (node (ref "JP16") (pin "13") (pinfunction "13_13") (pintype "passive"))
    )
    (net (code "233") (name "unconnected-(JP17-Pad2)") (class "Default")
      (node (ref "JP17") (pin "2") (pinfunction "2_2") (pintype "passive"))
    )
    (net (code "234") (name "unconnected-(JP17-Pad3)") (class "Default")
      (node (ref "JP17") (pin "3") (pinfunction "3_3") (pintype "passive"))
    )
    (net (code "235") (name "unconnected-(JP17-Pad4)") (class "Default")
      (node (ref "JP17") (pin "4") (pinfunction "4_4") (pintype "passive"))
    )
    (net (code "236") (name "unconnected-(JP17-Pad5)") (class "Default")
      (node (ref "JP17") (pin "5") (pinfunction "5_5") (pintype "passive"))
    )
    (net (code "237") (name "unconnected-(JP17-Pad6)") (class "Default")
      (node (ref "JP17") (pin "6") (pinfunction "6_6") (pintype "passive"))
    )
    (net (code "238") (name "unconnected-(JP17-Pad7)") (class "Default")
      (node (ref "JP17") (pin "7") (pinfunction "7_7") (pintype "passive"))
    )
    (net (code "239") (name "unconnected-(JP17-Pad8)") (class "Default")
      (node (ref "JP17") (pin "8") (pinfunction "8_8") (pintype "passive"))
    )
    (net (code "240") (name "unconnected-(JP17-Pad9)") (class "Default")
      (node (ref "JP17") (pin "9") (pinfunction "9_9") (pintype "passive"))
    )
    (net (code "241") (name "unconnected-(JP17-Pad10)") (class "Default")
      (node (ref "JP17") (pin "10") (pinfunction "10_10") (pintype "passive"))
    )
    (net (code "242") (name "unconnected-(JP17-Pad11)") (class "Default")
      (node (ref "JP17") (pin "11") (pinfunction "11_11") (pintype "passive"))
    )
    (net (code "243") (name "unconnected-(JP17-Pad12)") (class "Default")
      (node (ref "JP17") (pin "12") (pinfunction "12_12") (pintype "passive"))
    )
    (net (code "244") (name "unconnected-(JP17-Pad13)") (class "Default")
      (node (ref "JP17") (pin "13") (pinfunction "13_13") (pintype "passive"))
    )
    (net (code "245") (name "unconnected-(JP18-Pad2)") (class "Default")
      (node (ref "JP18") (pin "2") (pinfunction "2_2") (pintype "passive"))
    )
    (net (code "246") (name "unconnected-(JP18-Pad3)") (class "Default")
      (node (ref "JP18") (pin "3") (pinfunction "3_3") (pintype "passive"))
    )
    (net (code "247") (name "unconnected-(JP18-Pad4)") (class "Default")
      (node (ref "JP18") (pin "4") (pinfunction "4_4") (pintype "passive"))
    )
    (net (code "248") (name "unconnected-(JP18-Pad5)") (class "Default")
      (node (ref "JP18") (pin "5") (pinfunction "5_5") (pintype "passive"))
    )
    (net (code "249") (name "unconnected-(JP18-Pad6)") (class "Default")
      (node (ref "JP18") (pin "6") (pinfunction "6_6") (pintype "passive"))
    )
    (net (code "250") (name "unconnected-(JP18-Pad7)") (class "Default")
      (node (ref "JP18") (pin "7") (pinfunction "7_7") (pintype "passive"))
    )
    (net (code "251") (name "unconnected-(JP18-Pad8)") (class "Default")
      (node (ref "JP18") (pin "8") (pinfunction "8_8") (pintype "passive"))
    )
    (net (code "252") (name "unconnected-(JP18-Pad9)") (class "Default")
      (node (ref "JP18") (pin "9") (pinfunction "9_9") (pintype "passive"))
    )
    (net (code "253") (name "unconnected-(JP18-Pad10)") (class "Default")
      (node (ref "JP18") (pin "10") (pinfunction "10_10") (pintype "passive"))
    )
    (net (code "254") (name "unconnected-(JP18-Pad11)") (class "Default")
      (node (ref "JP18") (pin "11") (pinfunction "11_11") (pintype "passive"))
    )
    (net (code "255") (name "unconnected-(JP18-Pad12)") (class "Default")
      (node (ref "JP18") (pin "12") (pinfunction "12_12") (pintype "passive"))
    )
    (net (code "256") (name "unconnected-(JP18-Pad13)") (class "Default")
      (node (ref "JP18") (pin "13") (pinfunction "13_13") (pintype "passive"))
    )
    (net (code "257") (name "unconnected-(JP19-Pad2)") (class "Default")
      (node (ref "JP19") (pin "2") (pinfunction "2_2") (pintype "passive"))
    )
    (net (code "258") (name "unconnected-(JP19-Pad3)") (class "Default")
      (node (ref "JP19") (pin "3") (pinfunction "3_3") (pintype "passive"))
    )
    (net (code "259") (name "unconnected-(JP19-Pad4)") (class "Default")
      (node (ref "JP19") (pin "4") (pinfunction "4_4") (pintype "passive"))
    )
    (net (code "260") (name "unconnected-(JP19-Pad5)") (class "Default")
      (node (ref "JP19") (pin "5") (pinfunction "5_5") (pintype "passive"))
    )
    (net (code "261") (name "unconnected-(JP19-Pad6)") (class "Default")
      (node (ref "JP19") (pin "6") (pinfunction "6_6") (pintype "passive"))
    )
    (net (code "262") (name "unconnected-(JP19-Pad7)") (class "Default")
      (node (ref "JP19") (pin "7") (pinfunction "7_7") (pintype "passive"))
    )
    (net (code "263") (name "unconnected-(JP19-Pad8)") (class "Default")
      (node (ref "JP19") (pin "8") (pinfunction "8_8") (pintype "passive"))
    )
    (net (code "264") (name "unconnected-(JP19-Pad9)") (class "Default")
      (node (ref "JP19") (pin "9") (pinfunction "9_9") (pintype "passive"))
    )
    (net (code "265") (name "unconnected-(JP19-Pad10)") (class "Default")
      (node (ref "JP19") (pin "10") (pinfunction "10_10") (pintype "passive"))
    )
    (net (code "266") (name "unconnected-(JP19-Pad11)") (class "Default")
      (node (ref "JP19") (pin "11") (pinfunction "11_11") (pintype "passive"))
    )
    (net (code "267") (name "unconnected-(JP19-Pad12)") (class "Default")
      (node (ref "JP19") (pin "12") (pinfunction "12_12") (pintype "passive"))
    )
    (net (code "268") (name "unconnected-(JP19-Pad13)") (class "Default")
      (node (ref "JP19") (pin "13") (pinfunction "13_13") (pintype "passive"))
    )
    (net (code "269") (name "unconnected-(JP20-Pad2)") (class "Default")
      (node (ref "JP20") (pin "2") (pinfunction "2_2") (pintype "passive"))
    )
    (net (code "270") (name "unconnected-(JP20-Pad3)") (class "Default")
      (node (ref "JP20") (pin "3") (pinfunction "3_3") (pintype "passive"))
    )
    (net (code "271") (name "unconnected-(JP20-Pad4)") (class "Default")
      (node (ref "JP20") (pin "4") (pinfunction "4_4") (pintype "passive"))
    )
    (net (code "272") (name "unconnected-(JP20-Pad5)") (class "Default")
      (node (ref "JP20") (pin "5") (pinfunction "5_5") (pintype "passive"))
    )
    (net (code "273") (name "unconnected-(JP20-Pad6)") (class "Default")
      (node (ref "JP20") (pin "6") (pinfunction "6_6") (pintype "passive"))
    )
    (net (code "274") (name "unconnected-(JP20-Pad7)") (class "Default")
      (node (ref "JP20") (pin "7") (pinfunction "7_7") (pintype "passive"))
    )
    (net (code "275") (name "unconnected-(JP20-Pad8)") (class "Default")
      (node (ref "JP20") (pin "8") (pinfunction "8_8") (pintype "passive"))
    )
    (net (code "276") (name "unconnected-(JP20-Pad9)") (class "Default")
      (node (ref "JP20") (pin "9") (pinfunction "9_9") (pintype "passive"))
    )
    (net (code "277") (name "unconnected-(JP20-Pad10)") (class "Default")
      (node (ref "JP20") (pin "10") (pinfunction "10_10") (pintype "passive"))
    )
    (net (code "278") (name "unconnected-(JP20-Pad11)") (class "Default")
      (node (ref "JP20") (pin "11") (pinfunction "11_11") (pintype "passive"))
    )
    (net (code "279") (name "unconnected-(JP20-Pad12)") (class "Default")
      (node (ref "JP20") (pin "12") (pinfunction "12_12") (pintype "passive"))
    )
    (net (code "280") (name "unconnected-(JP20-Pad13)") (class "Default")
      (node (ref "JP20") (pin "13") (pinfunction "13_13") (pintype "passive"))
    )
    (net (code "281") (name "unconnected-(JP21-Pad1)") (class "Default")
      (node (ref "JP21") (pin "1") (pinfunction "1_1") (pintype "passive"))
    )
    (net (code "282") (name "unconnected-(JP21-Pad2)") (class "Default")
      (node (ref "JP21") (pin "2") (pinfunction "2_2") (pintype "passive"))
    )
    (net (code "283") (name "unconnected-(JP21-Pad3)") (class "Default")
      (node (ref "JP21") (pin "3") (pinfunction "3_3") (pintype "passive"))
    )
    (net (code "284") (name "unconnected-(JP21-Pad4)") (class "Default")
      (node (ref "JP21") (pin "4") (pinfunction "4_4") (pintype "passive"))
    )
    (net (code "285") (name "unconnected-(JP21-Pad5)") (class "Default")
      (node (ref "JP21") (pin "5") (pinfunction "5_5") (pintype "passive"))
    )
    (net (code "286") (name "unconnected-(JP21-Pad6)") (class "Default")
      (node (ref "JP21") (pin "6") (pinfunction "6_6") (pintype "passive"))
    )
    (net (code "287") (name "unconnected-(JP21-Pad7)") (class "Default")
      (node (ref "JP21") (pin "7") (pinfunction "7_7") (pintype "passive"))
    )
    (net (code "288") (name "unconnected-(JP21-Pad8)") (class "Default")
      (node (ref "JP21") (pin "8") (pinfunction "8_8") (pintype "passive"))
    )
    (net (code "289") (name "unconnected-(JP21-Pad9)") (class "Default")
      (node (ref "JP21") (pin "9") (pinfunction "9_9") (pintype "passive"))
    )
    (net (code "290") (name "unconnected-(JP21-Pad10)") (class "Default")
      (node (ref "JP21") (pin "10") (pinfunction "10_10") (pintype "passive"))
    )
    (net (code "291") (name "unconnected-(JP21-Pad11)") (class "Default")
      (node (ref "JP21") (pin "11") (pinfunction "11_11") (pintype "passive"))
    )
    (net (code "292") (name "unconnected-(JP21-Pad12)") (class "Default")
      (node (ref "JP21") (pin "12") (pinfunction "12_12") (pintype "passive"))
    )
    (net (code "293") (name "unconnected-(JP21-Pad13)") (class "Default")
      (node (ref "JP21") (pin "13") (pinfunction "13_13") (pintype "passive"))
    )
    (net (code "294") (name "unconnected-(JP21-Pad14)") (class "Default")
      (node (ref "JP21") (pin "14") (pinfunction "14_14") (pintype "passive"))
    )
    (net (code "295") (name "unconnected-(JP21-Pad15)") (class "Default")
      (node (ref "JP21") (pin "15") (pinfunction "15_15") (pintype "passive"))
    )
    (net (code "296") (name "unconnected-(JP21-Pad16)") (class "Default")
      (node (ref "JP21") (pin "16") (pinfunction "16_16") (pintype "passive"))
    )
    (net (code "297") (name "unconnected-(JP21-Pad17)") (class "Default")
      (node (ref "JP21") (pin "17") (pinfunction "17_17") (pintype "passive"))
    )
    (net (code "298") (name "unconnected-(JP21-Pad18)") (class "Default")
      (node (ref "JP21") (pin "18") (pinfunction "18_18") (pintype "passive"))
    )
    (net (code "299") (name "unconnected-(JP22-Pad1)") (class "Default")
      (node (ref "JP22") (pin "1") (pinfunction "1_1") (pintype "passive"))
    )
    (net (code "300") (name "unconnected-(JP22-Pad2)") (class "Default")
      (node (ref "JP22") (pin "2") (pinfunction "2_2") (pintype "passive"))
    )
    (net (code "301") (name "unconnected-(JP22-Pad3)") (class "Default")
      (node (ref "JP22") (pin "3") (pinfunction "3_3") (pintype "passive"))
    )
    (net (code "302") (name "unconnected-(JP22-Pad4)") (class "Default")
      (node (ref "JP22") (pin "4") (pinfunction "4_4") (pintype "passive"))
    )
    (net (code "303") (name "unconnected-(JP22-Pad5)") (class "Default")
      (node (ref "JP22") (pin "5") (pinfunction "5_5") (pintype "passive"))
    )
    (net (code "304") (name "unconnected-(JP22-Pad6)") (class "Default")
      (node (ref "JP22") (pin "6") (pinfunction "6_6") (pintype "passive"))
    )
    (net (code "305") (name "unconnected-(JP22-Pad7)") (class "Default")
      (node (ref "JP22") (pin "7") (pinfunction "7_7") (pintype "passive"))
    )
    (net (code "306") (name "unconnected-(JP22-Pad8)") (class "Default")
      (node (ref "JP22") (pin "8") (pinfunction "8_8") (pintype "passive"))
    )
    (net (code "307") (name "unconnected-(JP22-Pad9)") (class "Default")
      (node (ref "JP22") (pin "9") (pinfunction "9_9") (pintype "passive"))
    )
    (net (code "308") (name "unconnected-(JP22-Pad10)") (class "Default")
      (node (ref "JP22") (pin "10") (pinfunction "10_10") (pintype "passive"))
    )
    (net (code "309") (name "unconnected-(JP22-Pad11)") (class "Default")
      (node (ref "JP22") (pin "11") (pinfunction "11_11") (pintype "passive"))
    )
    (net (code "310") (name "unconnected-(JP22-Pad12)") (class "Default")
      (node (ref "JP22") (pin "12") (pinfunction "12_12") (pintype "passive"))
    )
    (net (code "311") (name "unconnected-(JP22-Pad13)") (class "Default")
      (node (ref "JP22") (pin "13") (pinfunction "13_13") (pintype "passive"))
    )
    (net (code "312") (name "unconnected-(JP22-Pad14)") (class "Default")
      (node (ref "JP22") (pin "14") (pinfunction "14_14") (pintype "passive"))
    )
    (net (code "313") (name "unconnected-(JP22-Pad15)") (class "Default")
      (node (ref "JP22") (pin "15") (pinfunction "15_15") (pintype "passive"))
    )
    (net (code "314") (name "unconnected-(JP22-Pad16)") (class "Default")
      (node (ref "JP22") (pin "16") (pinfunction "16_16") (pintype "passive"))
    )
    (net (code "315") (name "unconnected-(JP22-Pad17)") (class "Default")
      (node (ref "JP22") (pin "17") (pinfunction "17_17") (pintype "passive"))
    )
    (net (code "316") (name "unconnected-(JP22-Pad18)") (class "Default")
      (node (ref "JP22") (pin "18") (pinfunction "18_18") (pintype "passive"))
    )
    (net (code "317") (name "unconnected-(JP23-Pad1)") (class "Default")
      (node (ref "JP23") (pin "1") (pinfunction "1_1") (pintype "passive"))
    )
    (net (code "318") (name "unconnected-(JP23-Pad2)") (class "Default")
      (node (ref "JP23") (pin "2") (pinfunction "2_2") (pintype "passive"))
    )
    (net (code "319") (name "unconnected-(JP23-Pad3)") (class "Default")
      (node (ref "JP23") (pin "3") (pinfunction "3_3") (pintype "passive"))
    )
    (net (code "320") (name "unconnected-(JP23-Pad4)") (class "Default")
      (node (ref "JP23") (pin "4") (pinfunction "4_4") (pintype "passive"))
    )
    (net (code "321") (name "unconnected-(JP23-Pad5)") (class "Default")
      (node (ref "JP23") (pin "5") (pinfunction "5_5") (pintype "passive"))
    )
    (net (code "322") (name "unconnected-(JP23-Pad6)") (class "Default")
      (node (ref "JP23") (pin "6") (pinfunction "6_6") (pintype "passive"))
    )
    (net (code "323") (name "unconnected-(JP23-Pad7)") (class "Default")
      (node (ref "JP23") (pin "7") (pinfunction "7_7") (pintype "passive"))
    )
    (net (code "324") (name "unconnected-(JP23-Pad8)") (class "Default")
      (node (ref "JP23") (pin "8") (pinfunction "8_8") (pintype "passive"))
    )
    (net (code "325") (name "unconnected-(JP23-Pad9)") (class "Default")
      (node (ref "JP23") (pin "9") (pinfunction "9_9") (pintype "passive"))
    )
    (net (code "326") (name "unconnected-(JP23-Pad10)") (class "Default")
      (node (ref "JP23") (pin "10") (pinfunction "10_10") (pintype "passive"))
    )
    (net (code "327") (name "unconnected-(JP23-Pad11)") (class "Default")
      (node (ref "JP23") (pin "11") (pinfunction "11_11") (pintype "passive"))
    )
    (net (code "328") (name "unconnected-(JP23-Pad12)") (class "Default")
      (node (ref "JP23") (pin "12") (pinfunction "12_12") (pintype "passive"))
    )
    (net (code "329") (name "unconnected-(JP23-Pad13)") (class "Default")
      (node (ref "JP23") (pin "13") (pinfunction "13_13") (pintype "passive"))
    )
    (net (code "330") (name "unconnected-(JP23-Pad14)") (class "Default")
      (node (ref "JP23") (pin "14") (pinfunction "14_14") (pintype "passive"))
    )
    (net (code "331") (name "unconnected-(JP23-Pad15)") (class "Default")
      (node (ref "JP23") (pin "15") (pinfunction "15_15") (pintype "passive"))
    )
    (net (code "332") (name "unconnected-(JP23-Pad16)") (class "Default")
      (node (ref "JP23") (pin "16") (pinfunction "16_16") (pintype "passive"))
    )
    (net (code "333") (name "unconnected-(JP23-Pad17)") (class "Default")
      (node (ref "JP23") (pin "17") (pinfunction "17_17") (pintype "passive"))
    )
    (net (code "334") (name "unconnected-(JP23-Pad18)") (class "Default")
      (node (ref "JP23") (pin "18") (pinfunction "18_18") (pintype "passive"))
    )
    (net (code "335") (name "unconnected-(JP24-Pad1)") (class "Default")
      (node (ref "JP24") (pin "1") (pinfunction "1_1") (pintype "passive"))
    )
    (net (code "336") (name "unconnected-(JP24-Pad2)") (class "Default")
      (node (ref "JP24") (pin "2") (pinfunction "2_2") (pintype "passive"))
    )
    (net (code "337") (name "unconnected-(JP24-Pad3)") (class "Default")
      (node (ref "JP24") (pin "3") (pinfunction "3_3") (pintype "passive"))
    )
    (net (code "338") (name "unconnected-(JP24-Pad4)") (class "Default")
      (node (ref "JP24") (pin "4") (pinfunction "4_4") (pintype "passive"))
    )
    (net (code "339") (name "unconnected-(JP24-Pad5)") (class "Default")
      (node (ref "JP24") (pin "5") (pinfunction "5_5") (pintype "passive"))
    )
    (net (code "340") (name "unconnected-(JP24-Pad6)") (class "Default")
      (node (ref "JP24") (pin "6") (pinfunction "6_6") (pintype "passive"))
    )
    (net (code "341") (name "unconnected-(JP24-Pad7)") (class "Default")
      (node (ref "JP24") (pin "7") (pinfunction "7_7") (pintype "passive"))
    )
    (net (code "342") (name "unconnected-(JP24-Pad8)") (class "Default")
      (node (ref "JP24") (pin "8") (pinfunction "8_8") (pintype "passive"))
    )
    (net (code "343") (name "unconnected-(JP24-Pad9)") (class "Default")
      (node (ref "JP24") (pin "9") (pinfunction "9_9") (pintype "passive"))
    )
    (net (code "344") (name "unconnected-(JP24-Pad10)") (class "Default")
      (node (ref "JP24") (pin "10") (pinfunction "10_10") (pintype "passive"))
    )
    (net (code "345") (name "unconnected-(JP24-Pad11)") (class "Default")
      (node (ref "JP24") (pin "11") (pinfunction "11_11") (pintype "passive"))
    )
    (net (code "346") (name "unconnected-(JP24-Pad12)") (class "Default")
      (node (ref "JP24") (pin "12") (pinfunction "12_12") (pintype "passive"))
    )
    (net (code "347") (name "unconnected-(JP24-Pad13)") (class "Default")
      (node (ref "JP24") (pin "13") (pinfunction "13_13") (pintype "passive"))
    )
    (net (code "348") (name "unconnected-(JP24-Pad14)") (class "Default")
      (node (ref "JP24") (pin "14") (pinfunction "14_14") (pintype "passive"))
    )
    (net (code "349") (name "unconnected-(JP24-Pad15)") (class "Default")
      (node (ref "JP24") (pin "15") (pinfunction "15_15") (pintype "passive"))
    )
    (net (code "350") (name "unconnected-(JP24-Pad16)") (class "Default")
      (node (ref "JP24") (pin "16") (pinfunction "16_16") (pintype "passive"))
    )
    (net (code "351") (name "unconnected-(JP24-Pad17)") (class "Default")
      (node (ref "JP24") (pin "17") (pinfunction "17_17") (pintype "passive"))
    )
    (net (code "352") (name "unconnected-(JP24-Pad18)") (class "Default")
      (node (ref "JP24") (pin "18") (pinfunction "18_18") (pintype "passive"))
    )
    (net (code "353") (name "unconnected-(JP25-Pad1)") (class "Default")
      (node (ref "JP25") (pin "1") (pinfunction "1_1") (pintype "passive"))
    )
    (net (code "354") (name "unconnected-(JP25-Pad2)") (class "Default")
      (node (ref "JP25") (pin "2") (pinfunction "2_2") (pintype "passive"))
    )
    (net (code "355") (name "unconnected-(JP25-Pad3)") (class "Default")
      (node (ref "JP25") (pin "3") (pinfunction "3_3") (pintype "passive"))
    )
    (net (code "356") (name "unconnected-(JP25-Pad4)") (class "Default")
      (node (ref "JP25") (pin "4") (pinfunction "4_4") (pintype "passive"))
    )
    (net (code "357") (name "unconnected-(JP25-Pad5)") (class "Default")
      (node (ref "JP25") (pin "5") (pinfunction "5_5") (pintype "passive"))
    )
    (net (code "358") (name "unconnected-(JP25-Pad6)") (class "Default")
      (node (ref "JP25") (pin "6") (pinfunction "6_6") (pintype "passive"))
    )
    (net (code "359") (name "unconnected-(JP25-Pad7)") (class "Default")
      (node (ref "JP25") (pin "7") (pinfunction "7_7") (pintype "passive"))
    )
    (net (code "360") (name "unconnected-(JP25-Pad8)") (class "Default")
      (node (ref "JP25") (pin "8") (pinfunction "8_8") (pintype "passive"))
    )
    (net (code "361") (name "unconnected-(JP25-Pad9)") (class "Default")
      (node (ref "JP25") (pin "9") (pinfunction "9_9") (pintype "passive"))
    )
    (net (code "362") (name "unconnected-(JP25-Pad10)") (class "Default")
      (node (ref "JP25") (pin "10") (pinfunction "10_10") (pintype "passive"))
    )
    (net (code "363") (name "unconnected-(JP25-Pad11)") (class "Default")
      (node (ref "JP25") (pin "11") (pinfunction "11_11") (pintype "passive"))
    )
    (net (code "364") (name "unconnected-(JP25-Pad12)") (class "Default")
      (node (ref "JP25") (pin "12") (pinfunction "12_12") (pintype "passive"))
    )
    (net (code "365") (name "unconnected-(JP25-Pad13)") (class "Default")
      (node (ref "JP25") (pin "13") (pinfunction "13_13") (pintype "passive"))
    )
    (net (code "366") (name "unconnected-(JP25-Pad14)") (class "Default")
      (node (ref "JP25") (pin "14") (pinfunction "14_14") (pintype "passive"))
    )
    (net (code "367") (name "unconnected-(JP25-Pad15)") (class "Default")
      (node (ref "JP25") (pin "15") (pinfunction "15_15") (pintype "passive"))
    )
    (net (code "368") (name "unconnected-(JP25-Pad16)") (class "Default")
      (node (ref "JP25") (pin "16") (pinfunction "16_16") (pintype "passive"))
    )
    (net (code "369") (name "unconnected-(JP25-Pad17)") (class "Default")
      (node (ref "JP25") (pin "17") (pinfunction "17_17") (pintype "passive"))
    )
    (net (code "370") (name "unconnected-(JP25-Pad18)") (class "Default")
      (node (ref "JP25") (pin "18") (pinfunction "18_18") (pintype "passive"))
    )
    (net (code "371") (name "unconnected-(JP26-Pad1)") (class "Default")
      (node (ref "JP26") (pin "1") (pinfunction "1_1") (pintype "passive"))
    )
    (net (code "372") (name "unconnected-(JP26-Pad2)") (class "Default")
      (node (ref "JP26") (pin "2") (pinfunction "2_2") (pintype "passive"))
    )
    (net (code "373") (name "unconnected-(JP26-Pad3)") (class "Default")
      (node (ref "JP26") (pin "3") (pinfunction "3_3") (pintype "passive"))
    )
    (net (code "374") (name "unconnected-(JP26-Pad4)") (class "Default")
      (node (ref "JP26") (pin "4") (pinfunction "4_4") (pintype "passive"))
    )
    (net (code "375") (name "unconnected-(JP26-Pad5)") (class "Default")
      (node (ref "JP26") (pin "5") (pinfunction "5_5") (pintype "passive"))
    )
    (net (code "376") (name "unconnected-(JP26-Pad6)") (class "Default")
      (node (ref "JP26") (pin "6") (pinfunction "6_6") (pintype "passive"))
    )
    (net (code "377") (name "unconnected-(JP26-Pad7)") (class "Default")
      (node (ref "JP26") (pin "7") (pinfunction "7_7") (pintype "passive"))
    )
    (net (code "378") (name "unconnected-(JP26-Pad8)") (class "Default")
      (node (ref "JP26") (pin "8") (pinfunction "8_8") (pintype "passive"))
    )
    (net (code "379") (name "unconnected-(JP26-Pad9)") (class "Default")
      (node (ref "JP26") (pin "9") (pinfunction "9_9") (pintype "passive"))
    )
    (net (code "380") (name "unconnected-(JP26-Pad10)") (class "Default")
      (node (ref "JP26") (pin "10") (pinfunction "10_10") (pintype "passive"))
    )
    (net (code "381") (name "unconnected-(JP26-Pad11)") (class "Default")
      (node (ref "JP26") (pin "11") (pinfunction "11_11") (pintype "passive"))
    )
    (net (code "382") (name "unconnected-(JP26-Pad12)") (class "Default")
      (node (ref "JP26") (pin "12") (pinfunction "12_12") (pintype "passive"))
    )
    (net (code "383") (name "unconnected-(JP26-Pad13)") (class "Default")
      (node (ref "JP26") (pin "13") (pinfunction "13_13") (pintype "passive"))
    )
    (net (code "384") (name "unconnected-(JP26-Pad14)") (class "Default")
      (node (ref "JP26") (pin "14") (pinfunction "14_14") (pintype "passive"))
    )
    (net (code "385") (name "unconnected-(JP26-Pad15)") (class "Default")
      (node (ref "JP26") (pin "15") (pinfunction "15_15") (pintype "passive"))
    )
    (net (code "386") (name "unconnected-(JP26-Pad16)") (class "Default")
      (node (ref "JP26") (pin "16") (pinfunction "16_16") (pintype "passive"))
    )
    (net (code "387") (name "unconnected-(JP26-Pad17)") (class "Default")
      (node (ref "JP26") (pin "17") (pinfunction "17_17") (pintype "passive"))
    )
    (net (code "388") (name "unconnected-(JP26-Pad18)") (class "Default")
      (node (ref "JP26") (pin "18") (pinfunction "18_18") (pintype "passive"))
    )
    (net (code "389") (name "unconnected-(JP27-Pad1)") (class "Default")
      (node (ref "JP27") (pin "1") (pinfunction "1_1") (pintype "passive"))
    )
    (net (code "390") (name "unconnected-(JP27-Pad2)") (class "Default")
      (node (ref "JP27") (pin "2") (pinfunction "2_2") (pintype "passive"))
    )
    (net (code "391") (name "unconnected-(JP27-Pad3)") (class "Default")
      (node (ref "JP27") (pin "3") (pinfunction "3_3") (pintype "passive"))
    )
    (net (code "392") (name "unconnected-(JP27-Pad4)") (class "Default")
      (node (ref "JP27") (pin "4") (pinfunction "4_4") (pintype "passive"))
    )
    (net (code "393") (name "unconnected-(JP27-Pad5)") (class "Default")
      (node (ref "JP27") (pin "5") (pinfunction "5_5") (pintype "passive"))
    )
    (net (code "394") (name "unconnected-(JP27-Pad6)") (class "Default")
      (node (ref "JP27") (pin "6") (pinfunction "6_6") (pintype "passive"))
    )
    (net (code "395") (name "unconnected-(JP27-Pad7)") (class "Default")
      (node (ref "JP27") (pin "7") (pinfunction "7_7") (pintype "passive"))
    )
    (net (code "396") (name "unconnected-(JP27-Pad8)") (class "Default")
      (node (ref "JP27") (pin "8") (pinfunction "8_8") (pintype "passive"))
    )
    (net (code "397") (name "unconnected-(JP27-Pad9)") (class "Default")
      (node (ref "JP27") (pin "9") (pinfunction "9_9") (pintype "passive"))
    )
    (net (code "398") (name "unconnected-(JP27-Pad10)") (class "Default")
      (node (ref "JP27") (pin "10") (pinfunction "10_10") (pintype "passive"))
    )
    (net (code "399") (name "unconnected-(JP27-Pad11)") (class "Default")
      (node (ref "JP27") (pin "11") (pinfunction "11_11") (pintype "passive"))
    )
    (net (code "400") (name "unconnected-(JP27-Pad12)") (class "Default")
      (node (ref "JP27") (pin "12") (pinfunction "12_12") (pintype "passive"))
    )
    (net (code "401") (name "unconnected-(JP27-Pad13)") (class "Default")
      (node (ref "JP27") (pin "13") (pinfunction "13_13") (pintype "passive"))
    )
    (net (code "402") (name "unconnected-(JP27-Pad14)") (class "Default")
      (node (ref "JP27") (pin "14") (pinfunction "14_14") (pintype "passive"))
    )
    (net (code "403") (name "unconnected-(JP27-Pad15)") (class "Default")
      (node (ref "JP27") (pin "15") (pinfunction "15_15") (pintype "passive"))
    )
    (net (code "404") (name "unconnected-(JP27-Pad16)") (class "Default")
      (node (ref "JP27") (pin "16") (pinfunction "16_16") (pintype "passive"))
    )
    (net (code "405") (name "unconnected-(JP27-Pad17)") (class "Default")
      (node (ref "JP27") (pin "17") (pinfunction "17_17") (pintype "passive"))
    )
    (net (code "406") (name "unconnected-(JP27-Pad18)") (class "Default")
      (node (ref "JP27") (pin "18") (pinfunction "18_18") (pintype "passive"))
    )
    (net (code "407") (name "unconnected-(JP28-Pad1)") (class "Default")
      (node (ref "JP28") (pin "1") (pinfunction "1_1") (pintype "passive"))
    )
    (net (code "408") (name "unconnected-(JP28-Pad2)") (class "Default")
      (node (ref "JP28") (pin "2") (pinfunction "2_2") (pintype "passive"))
    )
    (net (code "409") (name "unconnected-(JP28-Pad3)") (class "Default")
      (node (ref "JP28") (pin "3") (pinfunction "3_3") (pintype "passive"))
    )
    (net (code "410") (name "unconnected-(JP28-Pad4)") (class "Default")
      (node (ref "JP28") (pin "4") (pinfunction "4_4") (pintype "passive"))
    )
    (net (code "411") (name "unconnected-(JP28-Pad5)") (class "Default")
      (node (ref "JP28") (pin "5") (pinfunction "5_5") (pintype "passive"))
    )
    (net (code "412") (name "unconnected-(JP28-Pad6)") (class "Default")
      (node (ref "JP28") (pin "6") (pinfunction "6_6") (pintype "passive"))
    )
    (net (code "413") (name "unconnected-(JP28-Pad7)") (class "Default")
      (node (ref "JP28") (pin "7") (pinfunction "7_7") (pintype "passive"))
    )
    (net (code "414") (name "unconnected-(JP28-Pad8)") (class "Default")
      (node (ref "JP28") (pin "8") (pinfunction "8_8") (pintype "passive"))
    )
    (net (code "415") (name "unconnected-(JP28-Pad9)") (class "Default")
      (node (ref "JP28") (pin "9") (pinfunction "9_9") (pintype "passive"))
    )
    (net (code "416") (name "unconnected-(JP28-Pad10)") (class "Default")
      (node (ref "JP28") (pin "10") (pinfunction "10_10") (pintype "passive"))
    )
    (net (code "417") (name "unconnected-(JP28-Pad11)") (class "Default")
      (node (ref "JP28") (pin "11") (pinfunction "11_11") (pintype "passive"))
    )
    (net (code "418") (name "unconnected-(JP28-Pad12)") (class "Default")
      (node (ref "JP28") (pin "12") (pinfunction "12_12") (pintype "passive"))
    )
    (net (code "419") (name "unconnected-(JP28-Pad13)") (class "Default")
      (node (ref "JP28") (pin "13") (pinfunction "13_13") (pintype "passive"))
    )
    (net (code "420") (name "unconnected-(JP28-Pad14)") (class "Default")
      (node (ref "JP28") (pin "14") (pinfunction "14_14") (pintype "passive"))
    )
    (net (code "421") (name "unconnected-(JP28-Pad15)") (class "Default")
      (node (ref "JP28") (pin "15") (pinfunction "15_15") (pintype "passive"))
    )
    (net (code "422") (name "unconnected-(JP28-Pad16)") (class "Default")
      (node (ref "JP28") (pin "16") (pinfunction "16_16") (pintype "passive"))
    )
    (net (code "423") (name "unconnected-(JP28-Pad17)") (class "Default")
      (node (ref "JP28") (pin "17") (pinfunction "17_17") (pintype "passive"))
    )
    (net (code "424") (name "unconnected-(JP28-Pad18)") (class "Default")
      (node (ref "JP28") (pin "18") (pinfunction "18_18") (pintype "passive"))
    )
    (net (code "425") (name "unconnected-(JP29-Pad1)") (class "Default")
      (node (ref "JP29") (pin "1") (pinfunction "1_1") (pintype "passive"))
    )
    (net (code "426") (name "unconnected-(JP29-Pad2)") (class "Default")
      (node (ref "JP29") (pin "2") (pinfunction "2_2") (pintype "passive"))
    )
    (net (code "427") (name "unconnected-(JP29-Pad3)") (class "Default")
      (node (ref "JP29") (pin "3") (pinfunction "3_3") (pintype "passive"))
    )
    (net (code "428") (name "unconnected-(JP29-Pad4)") (class "Default")
      (node (ref "JP29") (pin "4") (pinfunction "4_4") (pintype "passive"))
    )
    (net (code "429") (name "unconnected-(JP29-Pad5)") (class "Default")
      (node (ref "JP29") (pin "5") (pinfunction "5_5") (pintype "passive"))
    )
    (net (code "430") (name "unconnected-(JP29-Pad6)") (class "Default")
      (node (ref "JP29") (pin "6") (pinfunction "6_6") (pintype "passive"))
    )
    (net (code "431") (name "unconnected-(JP29-Pad7)") (class "Default")
      (node (ref "JP29") (pin "7") (pinfunction "7_7") (pintype "passive"))
    )
    (net (code "432") (name "unconnected-(JP29-Pad8)") (class "Default")
      (node (ref "JP29") (pin "8") (pinfunction "8_8") (pintype "passive"))
    )
    (net (code "433") (name "unconnected-(JP29-Pad9)") (class "Default")
      (node (ref "JP29") (pin "9") (pinfunction "9_9") (pintype "passive"))
    )
    (net (code "434") (name "unconnected-(JP29-Pad10)") (class "Default")
      (node (ref "JP29") (pin "10") (pinfunction "10_10") (pintype "passive"))
    )
    (net (code "435") (name "unconnected-(JP29-Pad11)") (class "Default")
      (node (ref "JP29") (pin "11") (pinfunction "11_11") (pintype "passive"))
    )
    (net (code "436") (name "unconnected-(JP29-Pad12)") (class "Default")
      (node (ref "JP29") (pin "12") (pinfunction "12_12") (pintype "passive"))
    )
    (net (code "437") (name "unconnected-(JP29-Pad13)") (class "Default")
      (node (ref "JP29") (pin "13") (pinfunction "13_13") (pintype "passive"))
    )
    (net (code "438") (name "unconnected-(JP29-Pad14)") (class "Default")
      (node (ref "JP29") (pin "14") (pinfunction "14_14") (pintype "passive"))
    )
    (net (code "439") (name "unconnected-(JP29-Pad15)") (class "Default")
      (node (ref "JP29") (pin "15") (pinfunction "15_15") (pintype "passive"))
    )
    (net (code "440") (name "unconnected-(JP29-Pad16)") (class "Default")
      (node (ref "JP29") (pin "16") (pinfunction "16_16") (pintype "passive"))
    )
    (net (code "441") (name "unconnected-(JP29-Pad17)") (class "Default")
      (node (ref "JP29") (pin "17") (pinfunction "17_17") (pintype "passive"))
    )
    (net (code "442") (name "unconnected-(JP29-Pad18)") (class "Default")
      (node (ref "JP29") (pin "18") (pinfunction "18_18") (pintype "passive"))
    )
    (net (code "443") (name "unconnected-(JP30-Pad1)") (class "Default")
      (node (ref "JP30") (pin "1") (pinfunction "1_1") (pintype "passive"))
    )
    (net (code "444") (name "unconnected-(JP30-Pad2)") (class "Default")
      (node (ref "JP30") (pin "2") (pinfunction "2_2") (pintype "passive"))
    )
    (net (code "445") (name "unconnected-(JP30-Pad3)") (class "Default")
      (node (ref "JP30") (pin "3") (pinfunction "3_3") (pintype "passive"))
    )
    (net (code "446") (name "unconnected-(JP30-Pad4)") (class "Default")
      (node (ref "JP30") (pin "4") (pinfunction "4_4") (pintype "passive"))
    )
    (net (code "447") (name "unconnected-(JP30-Pad5)") (class "Default")
      (node (ref "JP30") (pin "5") (pinfunction "5_5") (pintype "passive"))
    )
    (net (code "448") (name "unconnected-(JP30-Pad6)") (class "Default")
      (node (ref "JP30") (pin "6") (pinfunction "6_6") (pintype "passive"))
    )
    (net (code "449") (name "unconnected-(JP30-Pad7)") (class "Default")
      (node (ref "JP30") (pin "7") (pinfunction "7_7") (pintype "passive"))
    )
    (net (code "450") (name "unconnected-(JP30-Pad8)") (class "Default")
      (node (ref "JP30") (pin "8") (pinfunction "8_8") (pintype "passive"))
    )
    (net (code "451") (name "unconnected-(JP30-Pad9)") (class "Default")
      (node (ref "JP30") (pin "9") (pinfunction "9_9") (pintype "passive"))
    )
    (net (code "452") (name "unconnected-(JP30-Pad10)") (class "Default")
      (node (ref "JP30") (pin "10") (pinfunction "10_10") (pintype "passive"))
    )
    (net (code "453") (name "unconnected-(JP30-Pad11)") (class "Default")
      (node (ref "JP30") (pin "11") (pinfunction "11_11") (pintype "passive"))
    )
    (net (code "454") (name "unconnected-(JP30-Pad12)") (class "Default")
      (node (ref "JP30") (pin "12") (pinfunction "12_12") (pintype "passive"))
    )
    (net (code "455") (name "unconnected-(JP30-Pad13)") (class "Default")
      (node (ref "JP30") (pin "13") (pinfunction "13_13") (pintype "passive"))
    )
    (net (code "456") (name "unconnected-(JP30-Pad14)") (class "Default")
      (node (ref "JP30") (pin "14") (pinfunction "14_14") (pintype "passive"))
    )
    (net (code "457") (name "unconnected-(JP30-Pad15)") (class "Default")
      (node (ref "JP30") (pin "15") (pinfunction "15_15") (pintype "passive"))
    )
    (net (code "458") (name "unconnected-(JP30-Pad16)") (class "Default")
      (node (ref "JP30") (pin "16") (pinfunction "16_16") (pintype "passive"))
    )
    (net (code "459") (name "unconnected-(JP30-Pad17)") (class "Default")
      (node (ref "JP30") (pin "17") (pinfunction "17_17") (pintype "passive"))
    )
    (net (code "460") (name "unconnected-(JP31-Pad1)") (class "Default")
      (node (ref "JP31") (pin "1") (pinfunction "1_1") (pintype "passive"))
    )
    (net (code "461") (name "unconnected-(JP31-Pad2)") (class "Default")
      (node (ref "JP31") (pin "2") (pinfunction "2_2") (pintype "passive"))
    )
    (net (code "462") (name "unconnected-(JP31-Pad3)") (class "Default")
      (node (ref "JP31") (pin "3") (pinfunction "3_3") (pintype "passive"))
    )
    (net (code "463") (name "unconnected-(JP31-Pad4)") (class "Default")
      (node (ref "JP31") (pin "4") (pinfunction "4_4") (pintype "passive"))
    )
    (net (code "464") (name "unconnected-(JP31-Pad5)") (class "Default")
      (node (ref "JP31") (pin "5") (pinfunction "5_5") (pintype "passive"))
    )
    (net (code "465") (name "unconnected-(JP31-Pad6)") (class "Default")
      (node (ref "JP31") (pin "6") (pinfunction "6_6") (pintype "passive"))
    )
    (net (code "466") (name "unconnected-(JP31-Pad7)") (class "Default")
      (node (ref "JP31") (pin "7") (pinfunction "7_7") (pintype "passive"))
    )
    (net (code "467") (name "unconnected-(JP31-Pad8)") (class "Default")
      (node (ref "JP31") (pin "8") (pinfunction "8_8") (pintype "passive"))
    )
    (net (code "468") (name "unconnected-(JP31-Pad9)") (class "Default")
      (node (ref "JP31") (pin "9") (pinfunction "9_9") (pintype "passive"))
    )
    (net (code "469") (name "unconnected-(JP31-Pad10)") (class "Default")
      (node (ref "JP31") (pin "10") (pinfunction "10_10") (pintype "passive"))
    )
    (net (code "470") (name "unconnected-(JP31-Pad11)") (class "Default")
      (node (ref "JP31") (pin "11") (pinfunction "11_11") (pintype "passive"))
    )
    (net (code "471") (name "unconnected-(JP31-Pad12)") (class "Default")
      (node (ref "JP31") (pin "12") (pinfunction "12_12") (pintype "passive"))
    )
    (net (code "472") (name "unconnected-(JP31-Pad13)") (class "Default")
      (node (ref "JP31") (pin "13") (pinfunction "13_13") (pintype "passive"))
    )
    (net (code "473") (name "unconnected-(JP31-Pad14)") (class "Default")
      (node (ref "JP31") (pin "14") (pinfunction "14_14") (pintype "passive"))
    )
    (net (code "474") (name "unconnected-(JP31-Pad15)") (class "Default")
      (node (ref "JP31") (pin "15") (pinfunction "15_15") (pintype "passive"))
    )
    (net (code "475") (name "unconnected-(JP31-Pad16)") (class "Default")
      (node (ref "JP31") (pin "16") (pinfunction "16_16") (pintype "passive"))
    )
    (net (code "476") (name "unconnected-(JP31-Pad17)") (class "Default")
      (node (ref "JP31") (pin "17") (pinfunction "17_17") (pintype "passive"))
    )
  )
)
